# Charging_Cap_1p25kV.net
KiCad netlist of a schematic drawn in Altium Designer
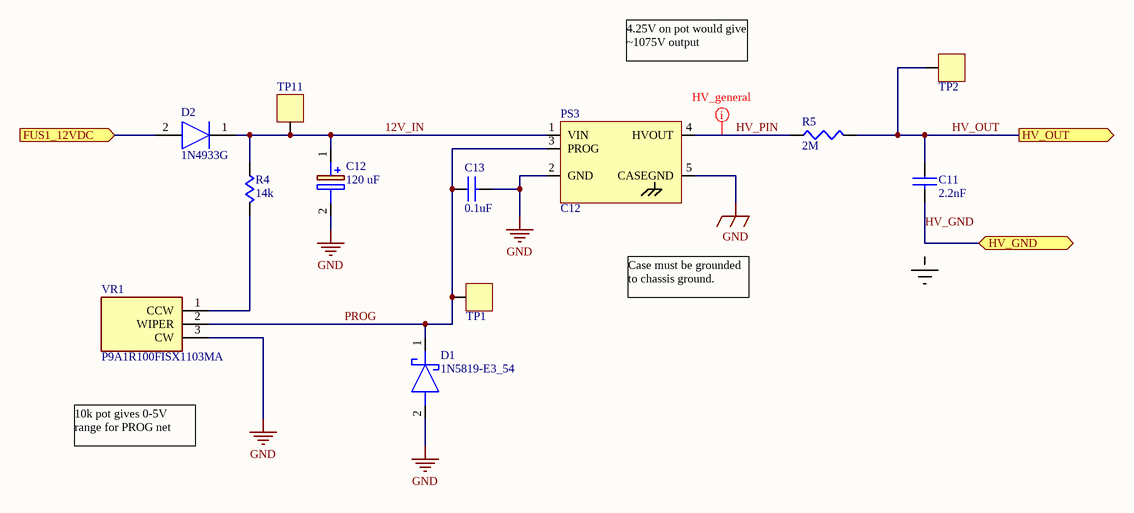
[diagram p0: Charging_Cap_1p25kV.SchDoc]

(export (version "E")
  (design (tool "Eeschema 10.0.6"))
  (components
    (comp (ref "C11")
      (value "2.2nF")
      (footprint "C331C222KHR5HA")
      (description "Multilayer Ceramic Capacitors MLCC - Leaded 3000V 2200pF X7R 10% LS=6.35mm")
      (libsource (lib "pulser_driver_symbols") (part "C331C222KHR5HA"))
    )
    (comp (ref "C12")
      (value "120 uF")
      (footprint "CAPPRD500W65D1000H1400")
      (description "Capacitor Polarised")
      (fields (field (name "MANUFACTURER_PART_NUMBER") "EEU-TP1V121"))
      (libsource (lib "pulser_driver_symbols") (part "EEU-TP1V121"))
    )
    (comp (ref "C13")
      (value "0.1uF")
      (footprint "C420C104K5R5TA7200")
      (description "CAP CER TH 0.1UF 50V X7R AXIAL")
      (libsource (lib "pulser_driver_symbols") (part "C420C104K5R5TA7200"))
    )
    (comp (ref "D1")
      (value "1N5819-E3_54")
      (footprint "DIOAD1405W86L465D235")
      (description "Schottky Diode")
      (fields
        (field (name "MANUFACTURER_PART_NUMBER") "1N5819-E3/54")
        (field (name "MOUSER PART NUMBER") "625-1N5819-E3")
      )
      (libsource (lib "pulser_driver_symbols") (part "1N5819-E3_54"))
    )
    (comp (ref "D2")
      (value "1N4933G")
      (footprint "DIOAD1405W86L465D235")
      (description "Rectifiers 50V 1A Fast")
      (fields (field (name "MOUSER PART NUMBER") "863-1N4933G"))
      (libsource (lib "pulser_driver_symbols") (part "1N4933G"))
    )
    (comp (ref "PS3")
      (value "C12")
      (footprint "C12")
      (description "MPN is C12, DC DC conv")
      (libsource (lib "pulser_driver_symbols") (part "C12"))
    )
    (comp (ref "R4")
      (value "14k")
      (footprint "MFR-25FBF52-14K")
      (description "RES TH 14K OHM 1% 1/4W AXIAL")
      (libsource (lib "pulser_driver_symbols") (part "MFR-25FBF52-14K"))
    )
    (comp (ref "R5")
      (value "2M")
      (footprint "HHV1WSJT-73-2M")
      (description "RES 2M OHM 5% 1W AXIAL")
      (libsource (lib "pulser_driver_symbols") (part "HHV1WSJT-73-2M"))
    )
    (comp (ref "TP1")
      (value "5261")
      (footprint "5261")
      (description "TEST POINT grabber (BLACK) - MINIATURE")
      (libsource (lib "pulser_driver_symbols") (part "5261"))
    )
    (comp (ref "TP2")
      (value "5261")
      (footprint "5261")
      (description "TEST POINT grabber (BLACK) - MINIATURE")
      (libsource (lib "pulser_driver_symbols") (part "5261"))
    )
    (comp (ref "TP11")
      (value "5261")
      (footprint "5261")
      (description "TEST POINT grabber (BLACK) - MINIATURE")
      (libsource (lib "") (part "5261_1"))
    )
    (comp (ref "VR1")
      (value "P9A1R100FISX1103MA")
      (footprint "P9A1R100FISX1103MA")
      (description "Variable Resistor 10K")
      (fields (field (name "MOUSER PART NUMBER") "72-P9A1RFISX1BB2103M"))
      (libsource (lib "pulser_driver_symbols") (part "P9A1R100FISX1103MA"))
    )
  )
  (nets
    (net (code "1") (name "/12V_IN") (class "Default")
      (node (ref "C12") (pin "1") (pinfunction "+_1") (pintype "passive"))
      (node (ref "D2") (pin "1") (pinfunction "K_1") (pintype "passive"))
      (node (ref "PS3") (pin "1") (pinfunction "VIN_1") (pintype "passive"))
      (node (ref "R4") (pin "1") (pinfunction "1_1") (pintype "passive"))
      (node (ref "TP11") (pin "1") (pinfunction "1_1") (pintype "passive"))
    )
    (net (code "2") (name "/FUS1_12VDC") (class "Default")
      (node (ref "D2") (pin "2") (pinfunction "A_2") (pintype "passive"))
    )
    (net (code "3") (name "/HV_GND") (class "Default")
      (node (ref "C11") (pin "2") (pinfunction "2_2") (pintype "passive"))
    )
    (net (code "4") (name "/HV_OUT") (class "Default")
      (node (ref "C11") (pin "1") (pinfunction "1_1") (pintype "passive"))
      (node (ref "R5") (pin "2") (pinfunction "2_2") (pintype "passive"))
      (node (ref "TP2") (pin "1") (pinfunction "1_1") (pintype "passive"))
    )
    (net (code "5") (name "/HV_PIN") (class "Default")
      (node (ref "PS3") (pin "4") (pinfunction "HVOUT_4") (pintype "passive"))
      (node (ref "R5") (pin "1") (pinfunction "1_1") (pintype "passive"))
    )
    (net (code "6") (name "/PROG") (class "Default")
      (node (ref "C13") (pin "1") (pinfunction "1_1") (pintype "passive"))
      (node (ref "D1") (pin "1") (pinfunction "K_1") (pintype "passive"))
      (node (ref "PS3") (pin "3") (pinfunction "PROG_3") (pintype "passive"))
      (node (ref "TP1") (pin "1") (pinfunction "1_1") (pintype "passive"))
      (node (ref "VR1") (pin "2") (pinfunction "WIPER_2") (pintype "passive"))
    )
    (net (code "7") (name "GND") (class "Default")
      (node (ref "C12") (pin "2") (pinfunction "-_2") (pintype "passive"))
      (node (ref "C13") (pin "2") (pinfunction "2_2") (pintype "passive"))
      (node (ref "D1") (pin "2") (pinfunction "A_2") (pintype "passive"))
      (node (ref "PS3") (pin "2") (pinfunction "GND_2") (pintype "passive"))
      (node (ref "PS3") (pin "5") (pinfunction "CASEGND_5") (pintype "passive"))
      (node (ref "VR1") (pin "3") (pinfunction "CW_3") (pintype "passive"))
    )
    (net (code "8") (name "Net-(VR1-CCW)") (class "Default")
      (node (ref "R4") (pin "2") (pinfunction "2_2") (pintype "passive"))
      (node (ref "VR1") (pin "1") (pinfunction "CCW_1") (pintype "passive"))
    )
  )
)
